# CellSelectModule.net
KiCad netlist of a schematic drawn in Altium Designer
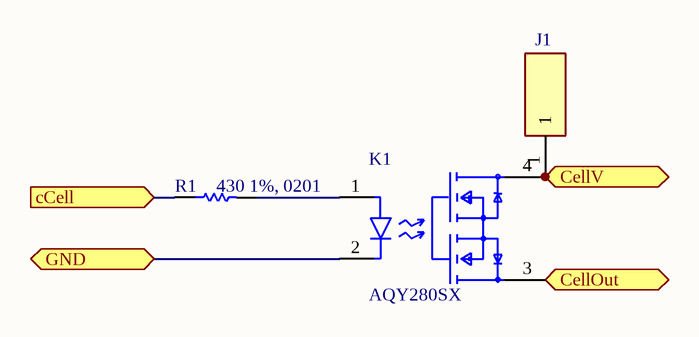
[diagram p0: CellSelectModule.SchDoc]

(export (version "E")
  (design (tool "Eeschema 10.0.6"))
  (components
    (comp (ref "J1")
      (value "TestPad")
      (footprint "SamacSys:TestPad")
      (description "Connector")
      (fields
        (field (name "MANUFACTURER_PART_NUMBER") "61300111121")
        (field (name "MOUSER PART NUMBER") "710-61300111121")
      )
      (libsource (lib "*") (part "61300111121"))
    )
    (comp (ref "K1")
      (value "AQY280SX")
      (footprint "FP-AQY280SX-MFG")
      (description "AQY280SX AQY Photomos Series 120 mA 350 V 25 Ohm SMT 1 Channel Solid State Relay -SOP-4")
      (libsource (lib "Altium Content Vault") (part "39108d2c2fe9c6c4263f1aa8ae40286"))
    )
    (comp (ref "R1")
      (value "430 1%, 0201")
      (footprint "RESC0603X26X15NL03T05")
      (fields (field (name "MANUFACTURER") "Panasonic") (field (name "PART NUMBER") "ERJ1GNF4302C"))
      (libsource (lib "Altium Content Vault") (part "RES"))
    )
  )
  (nets
    (net (code "1") (name "/CellOut") (class "Default")
      (node (ref "K1") (pin "3") (pinfunction "1_DRAIN_3") (pintype "passive"))
    )
    (net (code "2") (name "/CellV") (class "Default")
      (node (ref "J1") (pin "1") (pinfunction "1_1") (pintype "passive"))
      (node (ref "K1") (pin "4") (pinfunction "2_DRAIN_4") (pintype "passive"))
    )
    (net (code "3") (name "/GND") (class "Default")
      (node (ref "K1") (pin "2") (pinfunction "C_2") (pintype "passive"))
    )
    (net (code "4") (name "/cCell") (class "Default")
      (node (ref "R1") (pin "1") (pinfunction "1_1") (pintype "passive"))
    )
    (net (code "5") (name "Net-(K1-A)") (class "Default")
      (node (ref "K1") (pin "1") (pinfunction "A_1") (pintype "passive"))
      (node (ref "R1") (pin "2") (pinfunction "2_2") (pintype "passive"))
    )
  )
)
